# Quad-Thermocouple-Interface.net
KiCad netlist of a schematic drawn in EAGLE
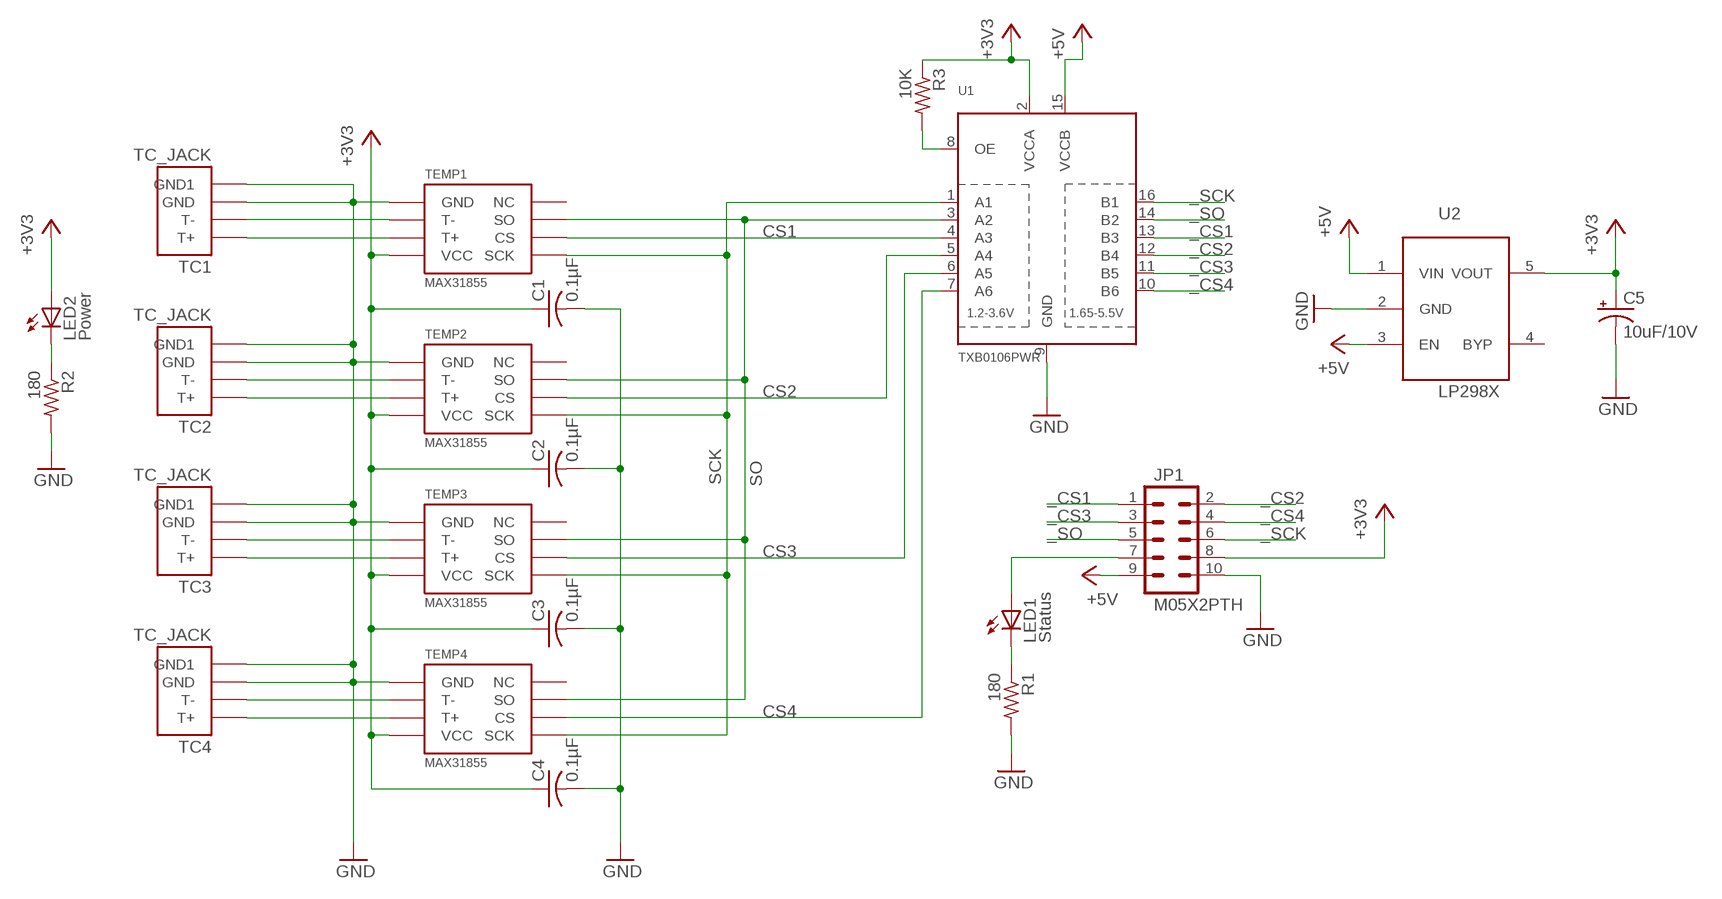
[diagram p0: schematic, sheet 1]

(export (version "E")
  (design (tool "Eeschema 10.0.6"))
  (components
    (comp (ref "C1")
      (value "0.1µF")
      (footprint "eagle-import:C0603")
      (libsource (lib "eagle-import") (part "C-USC0603"))
    )
    (comp (ref "C2")
      (value "0.1µF")
      (footprint "eagle-import:C0603")
      (libsource (lib "eagle-import") (part "C-USC0603"))
    )
    (comp (ref "C3")
      (value "0.1µF")
      (footprint "eagle-import:C0603")
      (libsource (lib "eagle-import") (part "C-USC0603"))
    )
    (comp (ref "C4")
      (value "0.1µF")
      (footprint "eagle-import:C0603")
      (libsource (lib "eagle-import") (part "C-USC0603"))
    )
    (comp (ref "C5")
      (value "10uF/10V")
      (footprint "eagle-import:A_3216-18R")
      (libsource (lib "eagle-import") (part "CPOL-USA/3216-18R"))
    )
    (comp (ref "JP1")
      (value "M05X2PTH")
      (footprint "eagle-import:AVR_ICSP")
      (libsource (lib "eagle-import") (part "M05X2PTH"))
    )
    (comp (ref "LED1")
      (value "Status")
      (footprint "eagle-import:CHIPLED_0805")
      (libsource (lib "eagle-import") (part "LEDCHIPLED_0805"))
    )
    (comp (ref "LED2")
      (value "Power")
      (footprint "eagle-import:CHIPLED_0805")
      (libsource (lib "eagle-import") (part "LEDCHIPLED_0805"))
    )
    (comp (ref "R1")
      (value "180")
      (footprint "eagle-import:R0603")
      (libsource (lib "eagle-import") (part "R-US_R0603"))
    )
    (comp (ref "R2")
      (value "180")
      (footprint "eagle-import:R0603")
      (libsource (lib "eagle-import") (part "R-US_R0603"))
    )
    (comp (ref "R3")
      (value "10K")
      (footprint "eagle-import:R0603")
      (libsource (lib "eagle-import") (part "R-US_R0603"))
    )
    (comp (ref "TC1")
      (value "TC_JACK")
      (footprint "eagle-import:TC_JACK")
      (libsource (lib "eagle-import") (part "TC_JACK"))
    )
    (comp (ref "TC2")
      (value "TC_JACK")
      (footprint "eagle-import:TC_JACK")
      (libsource (lib "eagle-import") (part "TC_JACK"))
    )
    (comp (ref "TC3")
      (value "TC_JACK")
      (footprint "eagle-import:TC_JACK")
      (libsource (lib "eagle-import") (part "TC_JACK"))
    )
    (comp (ref "TC4")
      (value "TC_JACK")
      (footprint "eagle-import:TC_JACK")
      (libsource (lib "eagle-import") (part "TC_JACK"))
    )
    (comp (ref "TEMP1")
      (value "MAX31855")
      (footprint "eagle-import:SOIC-8")
      (libsource (lib "eagle-import") (part "MAX6675MAX31855"))
    )
    (comp (ref "TEMP2")
      (value "MAX31855")
      (footprint "eagle-import:SOIC-8")
      (libsource (lib "eagle-import") (part "MAX6675MAX31855"))
    )
    (comp (ref "TEMP3")
      (value "MAX31855")
      (footprint "eagle-import:SOIC-8")
      (libsource (lib "eagle-import") (part "MAX6675MAX31855"))
    )
    (comp (ref "TEMP4")
      (value "MAX31855")
      (footprint "eagle-import:SOIC-8")
      (libsource (lib "eagle-import") (part "MAX6675MAX31855"))
    )
    (comp (ref "U1")
      (value "TXB0106PWR")
      (footprint "eagle-import:TSSOP16")
      (libsource (lib "eagle-import") (part "TXB0106PWR"))
    )
    (comp (ref "U2")
      (value "LP298XS")
      (footprint "eagle-import:SOT23-5L")
      (libsource (lib "eagle-import") (part "LP298XS"))
    )
  )
  (nets
    (net (code "1") (name "+3V3") (class "Default")
      (node (ref "C1") (pin "1") (pinfunction "1_1") (pintype "passive"))
      (node (ref "C2") (pin "1") (pinfunction "1_1") (pintype "passive"))
      (node (ref "C3") (pin "1") (pinfunction "1_1") (pintype "passive"))
      (node (ref "C4") (pin "1") (pinfunction "1_1") (pintype "passive"))
      (node (ref "C5") (pin "+") (pinfunction "+_+") (pintype "passive"))
      (node (ref "JP1") (pin "8") (pinfunction "8_8") (pintype "passive"))
      (node (ref "LED2") (pin "A") (pinfunction "A_A") (pintype "passive"))
      (node (ref "R3") (pin "1") (pinfunction "1_1") (pintype "passive"))
      (node (ref "TEMP1") (pin "VCC") (pinfunction "VCC_VCC") (pintype "bidirectional"))
      (node (ref "TEMP2") (pin "VCC") (pinfunction "VCC_VCC") (pintype "bidirectional"))
      (node (ref "TEMP3") (pin "VCC") (pinfunction "VCC_VCC") (pintype "bidirectional"))
      (node (ref "TEMP4") (pin "VCC") (pinfunction "VCC_VCC") (pintype "bidirectional"))
      (node (ref "U1") (pin "2") (pinfunction "VCCA_2") (pintype "bidirectional"))
      (node (ref "U2") (pin "5") (pinfunction "VOUT_5") (pintype "bidirectional"))
    )
    (net (code "2") (name "+5V") (class "Default")
      (node (ref "JP1") (pin "9") (pinfunction "9_9") (pintype "passive"))
      (node (ref "U1") (pin "15") (pinfunction "VCCB_15") (pintype "bidirectional"))
      (node (ref "U2") (pin "1") (pinfunction "VIN_1") (pintype "bidirectional"))
      (node (ref "U2") (pin "3") (pinfunction "EN_3") (pintype "bidirectional"))
    )
    (net (code "3") (name "/CS1") (class "Default")
      (node (ref "TEMP1") (pin "CS") (pinfunction "CS_CS") (pintype "bidirectional"))
      (node (ref "U1") (pin "4") (pinfunction "A3_4") (pintype "bidirectional"))
    )
    (net (code "4") (name "/CS2") (class "Default")
      (node (ref "TEMP2") (pin "CS") (pinfunction "CS_CS") (pintype "bidirectional"))
      (node (ref "U1") (pin "5") (pinfunction "A4_5") (pintype "bidirectional"))
    )
    (net (code "5") (name "/CS3") (class "Default")
      (node (ref "TEMP3") (pin "CS") (pinfunction "CS_CS") (pintype "bidirectional"))
      (node (ref "U1") (pin "6") (pinfunction "A5_6") (pintype "bidirectional"))
    )
    (net (code "6") (name "/CS4") (class "Default")
      (node (ref "TEMP4") (pin "CS") (pinfunction "CS_CS") (pintype "bidirectional"))
      (node (ref "U1") (pin "7") (pinfunction "A6_7") (pintype "bidirectional"))
    )
    (net (code "7") (name "/SCK") (class "Default")
      (node (ref "TEMP1") (pin "SCK") (pinfunction "SCK_SCK") (pintype "bidirectional"))
      (node (ref "TEMP2") (pin "SCK") (pinfunction "SCK_SCK") (pintype "bidirectional"))
      (node (ref "TEMP3") (pin "SCK") (pinfunction "SCK_SCK") (pintype "bidirectional"))
      (node (ref "TEMP4") (pin "SCK") (pinfunction "SCK_SCK") (pintype "bidirectional"))
      (node (ref "U1") (pin "1") (pinfunction "A1_1") (pintype "bidirectional"))
    )
    (net (code "8") (name "/SO") (class "Default")
      (node (ref "TEMP1") (pin "SO") (pinfunction "SO_SO") (pintype "bidirectional"))
      (node (ref "TEMP2") (pin "SO") (pinfunction "SO_SO") (pintype "bidirectional"))
      (node (ref "TEMP3") (pin "SO") (pinfunction "SO_SO") (pintype "bidirectional"))
      (node (ref "TEMP4") (pin "SO") (pinfunction "SO_SO") (pintype "bidirectional"))
      (node (ref "U1") (pin "3") (pinfunction "A2_3") (pintype "bidirectional"))
    )
    (net (code "9") (name "/_CS1") (class "Default")
      (node (ref "JP1") (pin "1") (pinfunction "1_1") (pintype "passive"))
      (node (ref "U1") (pin "13") (pinfunction "B3_13") (pintype "bidirectional"))
    )
    (net (code "10") (name "/_CS2") (class "Default")
      (node (ref "JP1") (pin "2") (pinfunction "2_2") (pintype "passive"))
      (node (ref "U1") (pin "12") (pinfunction "B4_12") (pintype "bidirectional"))
    )
    (net (code "11") (name "/_CS3") (class "Default")
      (node (ref "JP1") (pin "3") (pinfunction "3_3") (pintype "passive"))
      (node (ref "U1") (pin "11") (pinfunction "B5_11") (pintype "bidirectional"))
    )
    (net (code "12") (name "/_CS4") (class "Default")
      (node (ref "JP1") (pin "4") (pinfunction "4_4") (pintype "passive"))
      (node (ref "U1") (pin "10") (pinfunction "B6_10") (pintype "bidirectional"))
    )
    (net (code "13") (name "/_SCK") (class "Default")
      (node (ref "JP1") (pin "6") (pinfunction "6_6") (pintype "passive"))
      (node (ref "U1") (pin "16") (pinfunction "B1_16") (pintype "bidirectional"))
    )
    (net (code "14") (name "/_SO") (class "Default")
      (node (ref "JP1") (pin "5") (pinfunction "5_5") (pintype "passive"))
      (node (ref "U1") (pin "14") (pinfunction "B2_14") (pintype "bidirectional"))
    )
    (net (code "15") (name "GND") (class "Default")
      (node (ref "C1") (pin "2") (pinfunction "2_2") (pintype "passive"))
      (node (ref "C2") (pin "2") (pinfunction "2_2") (pintype "passive"))
      (node (ref "C3") (pin "2") (pinfunction "2_2") (pintype "passive"))
      (node (ref "C4") (pin "2") (pinfunction "2_2") (pintype "passive"))
      (node (ref "C5") (pin "-") (pinfunction "-_-") (pintype "passive"))
      (node (ref "JP1") (pin "10") (pinfunction "10_10") (pintype "passive"))
      (node (ref "R1") (pin "2") (pinfunction "2_2") (pintype "passive"))
      (node (ref "R2") (pin "2") (pinfunction "2_2") (pintype "passive"))
      (node (ref "TC1") (pin "P$1") (pinfunction "GND_P$1") (pintype "bidirectional"))
      (node (ref "TC1") (pin "P$2") (pinfunction "GND1_P$2") (pintype "bidirectional"))
      (node (ref "TC2") (pin "P$1") (pinfunction "GND_P$1") (pintype "bidirectional"))
      (node (ref "TC2") (pin "P$2") (pinfunction "GND1_P$2") (pintype "bidirectional"))
      (node (ref "TC3") (pin "P$1") (pinfunction "GND_P$1") (pintype "bidirectional"))
      (node (ref "TC3") (pin "P$2") (pinfunction "GND1_P$2") (pintype "bidirectional"))
      (node (ref "TC4") (pin "P$1") (pinfunction "GND_P$1") (pintype "bidirectional"))
      (node (ref "TC4") (pin "P$2") (pinfunction "GND1_P$2") (pintype "bidirectional"))
      (node (ref "TEMP1") (pin "GND") (pinfunction "GND_GND") (pintype "bidirectional"))
      (node (ref "TEMP2") (pin "GND") (pinfunction "GND_GND") (pintype "bidirectional"))
      (node (ref "TEMP3") (pin "GND") (pinfunction "GND_GND") (pintype "bidirectional"))
      (node (ref "TEMP4") (pin "GND") (pinfunction "GND_GND") (pintype "bidirectional"))
      (node (ref "U1") (pin "9") (pinfunction "GND_9") (pintype "bidirectional"))
      (node (ref "U2") (pin "2") (pinfunction "GND_2") (pintype "bidirectional"))
    )
    (net (code "16") (name "Net-(JP1-Pad7)") (class "Default")
      (node (ref "JP1") (pin "7") (pinfunction "7_7") (pintype "passive"))
      (node (ref "LED1") (pin "A") (pinfunction "A_A") (pintype "passive"))
    )
    (net (code "17") (name "Net-(LED1-PadC)") (class "Default")
      (node (ref "LED1") (pin "C") (pinfunction "C_C") (pintype "passive"))
      (node (ref "R1") (pin "1") (pinfunction "1_1") (pintype "passive"))
    )
    (net (code "18") (name "Net-(LED2-PadC)") (class "Default")
      (node (ref "LED2") (pin "C") (pinfunction "C_C") (pintype "passive"))
      (node (ref "R2") (pin "1") (pinfunction "1_1") (pintype "passive"))
    )
    (net (code "19") (name "Net-(TC1-PadT+)") (class "Default")
      (node (ref "TC1") (pin "T+") (pinfunction "T+_T+") (pintype "bidirectional"))
      (node (ref "TEMP1") (pin "T+") (pinfunction "T+_T+") (pintype "bidirectional"))
    )
    (net (code "20") (name "Net-(TC1-PadT-)") (class "Default")
      (node (ref "TC1") (pin "T-") (pinfunction "T-_T-") (pintype "bidirectional"))
      (node (ref "TEMP1") (pin "T-") (pinfunction "T-_T-") (pintype "bidirectional"))
    )
    (net (code "21") (name "Net-(TC2-PadT+)") (class "Default")
      (node (ref "TC2") (pin "T+") (pinfunction "T+_T+") (pintype "bidirectional"))
      (node (ref "TEMP2") (pin "T+") (pinfunction "T+_T+") (pintype "bidirectional"))
    )
    (net (code "22") (name "Net-(TC2-PadT-)") (class "Default")
      (node (ref "TC2") (pin "T-") (pinfunction "T-_T-") (pintype "bidirectional"))
      (node (ref "TEMP2") (pin "T-") (pinfunction "T-_T-") (pintype "bidirectional"))
    )
    (net (code "23") (name "Net-(TC3-PadT+)") (class "Default")
      (node (ref "TC3") (pin "T+") (pinfunction "T+_T+") (pintype "bidirectional"))
      (node (ref "TEMP3") (pin "T+") (pinfunction "T+_T+") (pintype "bidirectional"))
    )
    (net (code "24") (name "Net-(TC3-PadT-)") (class "Default")
      (node (ref "TC3") (pin "T-") (pinfunction "T-_T-") (pintype "bidirectional"))
      (node (ref "TEMP3") (pin "T-") (pinfunction "T-_T-") (pintype "bidirectional"))
    )
    (net (code "25") (name "Net-(TC4-PadT+)") (class "Default")
      (node (ref "TC4") (pin "T+") (pinfunction "T+_T+") (pintype "bidirectional"))
      (node (ref "TEMP4") (pin "T+") (pinfunction "T+_T+") (pintype "bidirectional"))
    )
    (net (code "26") (name "Net-(TC4-PadT-)") (class "Default")
      (node (ref "TC4") (pin "T-") (pinfunction "T-_T-") (pintype "bidirectional"))
      (node (ref "TEMP4") (pin "T-") (pinfunction "T-_T-") (pintype "bidirectional"))
    )
    (net (code "27") (name "Net-(U1-OE)") (class "Default")
      (node (ref "R3") (pin "2") (pinfunction "2_2") (pintype "passive"))
      (node (ref "U1") (pin "8") (pinfunction "OE_8") (pintype "bidirectional"))
    )
    (net (code "28") (name "unconnected-(TEMP1-PadNC)") (class "Default")
      (node (ref "TEMP1") (pin "NC") (pinfunction "NC_NC") (pintype "no_connect"))
    )
    (net (code "29") (name "unconnected-(TEMP2-PadNC)") (class "Default")
      (node (ref "TEMP2") (pin "NC") (pinfunction "NC_NC") (pintype "no_connect"))
    )
    (net (code "30") (name "unconnected-(TEMP3-PadNC)") (class "Default")
      (node (ref "TEMP3") (pin "NC") (pinfunction "NC_NC") (pintype "no_connect"))
    )
    (net (code "31") (name "unconnected-(TEMP4-PadNC)") (class "Default")
      (node (ref "TEMP4") (pin "NC") (pinfunction "NC_NC") (pintype "no_connect"))
    )
    (net (code "32") (name "unconnected-(U2-BYP-Pad4)") (class "Default")
      (node (ref "U2") (pin "4") (pinfunction "BYP_4") (pintype "bidirectional"))
    )
  )
)
